# AFE_Channel_1.net
KiCad netlist of a schematic drawn in Altium Designer
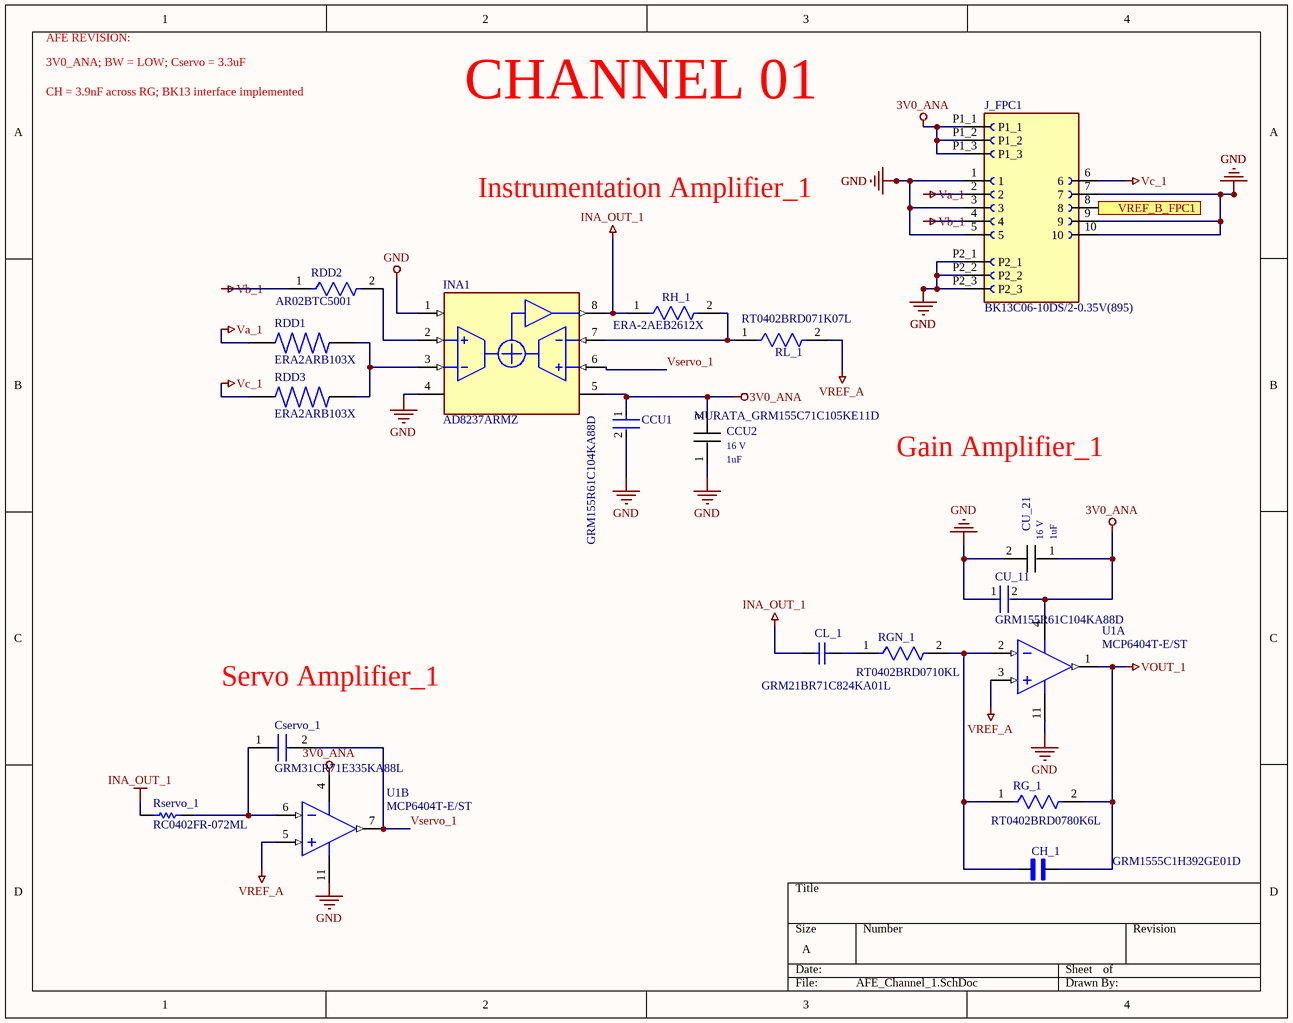
[diagram p0: AFE_Channel_1.SchDoc]

(export (version "E")
  (design (tool "Eeschema 10.0.6"))
  (components
    (comp (ref "CCU1")
      (value "GRM155R61C104KA88D")
      (footprint "96DF66F8-B997-472F-A885-42BCAAE661B2_FP-GRM155-0_05-IPC_C:FP-GRM155-0_05-IPC_C")
      (description "CAP CER 0.1UF 16V X5R 0402")
      (fields (field (name "VOLTAGE") "16V") (field (name "TOLERANCE") "10%"))
      (libsource (lib "EMG_Controlled_R5") (part "EMG_R5_CCU1"))
    )
    (comp (ref "CCU2")
      (value "MURATA_GRM155C71C105KE11D")
      (footprint "MURATA_GRM155C71C105KE11D_0:*MURATA_GRM155C71C105KE11D_0")
      (description "Murata GRM155C71C105KE11D: 1 uF 16 V X7S +/-10%, 0402/1005 metric")
      (fields (field (name "MF") "Murata") (field (name "MP") "GRM155C71C105KE11D"))
      (libsource (lib "EMG_Controlled_R5") (part "EMG_R5_CCU2"))
    )
    (comp (ref "CH_1")
      (value "GRM1555C1H392GE01D")
      (footprint "GRM1555C1H392GE01D_0:CAPC1005X55N")
      (description "SMD capacitor C0G(EIA) with capacitance 3900pF Tol.2%. Rated voltage 50Vdc 125C")
      (fields (field (name "MF") "Murata Electronics"))
      (libsource (lib "EMG_Controlled_R5") (part "EMG_R5_CH_1"))
    )
    (comp (ref "CL_1")
      (value "GRM21BR71C824KA01L")
      (footprint "987105EF-01FA-4198-A59F-44D3B68BB40E_CAPC2013X135X45ML10T25:CAPC2013X135X45ML10T25")
      (fields (field (name "MANUFACTURER") "Murata"))
      (libsource (lib "EMG_Controlled_R5") (part "EMG_R5_CL_1"))
    )
    (comp (ref "Cservo_1")
      (value "GRM31CR71E335KA88L")
      (footprint "SamacSys:GRM31x")
      (description "Capacitor")
      (fields
        (field (name "MOUSER PART NUMBER") "81-GRM31CR71E335KA8L")
        (field (name "MANUFACTURER") "Murata")
      )
      (libsource (lib "EMG_Controlled_R5") (part "EMG_R5_Cservo_1"))
    )
    (comp (ref "CU_11")
      (value "GRM155R61C104KA88D")
      (footprint "96DF66F8-B997-472F-A885-42BCAAE661B2_FP-GRM155-0_05-IPC_C:FP-GRM155-0_05-IPC_C")
      (description "CAP CER 0.1UF 16V X5R 0402")
      (fields (field (name "VOLTAGE") "16V") (field (name "TOLERANCE") "10%"))
      (libsource (lib "EMG_Controlled_R5") (part "EMG_R5_CU_11"))
    )
    (comp (ref "CU_21")
      (value "MURATA_GRM155C71C105KE11D")
      (footprint "MURATA_GRM155C71C105KE11D_0:*MURATA_GRM155C71C105KE11D_0")
      (description "Murata GRM155C71C105KE11D: 1 uF 16 V X7S +/-10%, 0402/1005 metric")
      (fields (field (name "MF") "Murata") (field (name "MP") "GRM155C71C105KE11D"))
      (libsource (lib "EMG_Controlled_R5") (part "EMG_R5_CU_21"))
    )
    (comp (ref "INA1")
      (value "AD8237ARMZ")
      (footprint "EMG_AD8237_R3:EMG_AD8237_R3_MSOP8")
      (description "Micropower, Zero Drift, True Rail-to-Rail Instrumentation Amplifier")
      (fields (field (name "MF") "Analog Devices"))
      (libsource (lib "EMG_Controlled_R5") (part "EMG_R5_INA1"))
    )
    (comp (ref "J_FPC1")
      (value "BK13C06-10DS/2-0.35V(895)")
      (footprint "BK13C06-10DS_2-0.35V_895__0:HIROSE_BK13C06-10DS/2-0.35V(895)")
      (description "10 Position Connector Receptacle, Center Strip Contacts Surface Mount Gold")
      (fields (field (name "MF") "Hirose Electric Co Ltd"))
      (libsource (lib "EMG_Controlled_R5") (part "EMG_R5_J_FPC1"))
    )
    (comp (ref "RDD1")
      (value "ERA2ARB103X")
      (footprint "ERA2ARB103X_0:RES_ERA2ARB103X")
      (libsource (lib "EMG_Controlled_R5") (part "EMG_R5_RDD1"))
    )
    (comp (ref "RDD2")
      (value "AR02BTC5001")
      (footprint "7D606042-220B-45EE-95DD-CA1A974E4C0D_FP-AC0402-MFG:FP-AC0402-MFG")
      (description "-55℃~+155℃ 50V 5kΩ 63mW Thin Film Resistor ±0.1% ±25ppm/℃ 0402 Chip Resistor - Surface Mount ROH")
      (fields
        (field (name "MANUFACTURER") "Viking Tech")
        (field (name "OCTOPART") "https://octopart.com/datasheet/viking-tech/AR02BTC5001")
      )
      (libsource (lib "EMG_Controlled_R5") (part "EMG_R5_RDD2"))
    )
    (comp (ref "RDD3")
      (value "ERA2ARB103X")
      (footprint "ERA2ARB103X_0:RES_ERA2ARB103X")
      (libsource (lib "EMG_Controlled_R5") (part "EMG_R5_RDD3"))
    )
    (comp (ref "RGN_1")
      (value "RT0402BRD0710KL")
      (footprint "B876F212-A29A-4983-9BB8-539D1BA2EBA1_FP-RT0402-MFG:FP-RT0402-MFG")
      (description "RES 10.0K OHM 1/16W .1% SMD 0402")
      (fields
        (field (name "MANUFACTURER") "Yageo")
        (field (name "OCTOPART") "https://octopart.com/rt0402brd0710kl-yageo-1181432")
      )
      (libsource (lib "EMG_Controlled_R5") (part "EMG_R5_RGN_1"))
    )
    (comp (ref "RG_1")
      (value "RT0402BRD0780K6L")
      (footprint "B876F212-A29A-4983-9BB8-539D1BA2EBA1_FP-RT0402-MFG:FP-RT0402-MFG")
      (description "RES SMD 80.6KOHM 0.1% 1/16W 0402")
      (fields
        (field (name "MANUFACTURER") "Yageo")
        (field (name "OCTOPART") "https://octopart.com/rt0402brd0780k6l-yageo-1468076")
      )
      (libsource (lib "EMG_Controlled_R5") (part "EMG_R5_RG_1"))
    )
    (comp (ref "RH_1")
      (value "ERA-2AEB2612X")
      (footprint "1CBBEC27-AD79-48E8-A701-2E235EA9F8F2_FP-AC0402-IPC_A:FP-AC0402-IPC_A")
      (description "RES 26.1kΩ ±0.1% 0.063W 0402")
      (fields (field (name "TOLERANCE") "0.1%") (field (name "MANUFACTURER") "PANASONIC"))
      (libsource (lib "EMG_Controlled_R5") (part "EMG_R5_RH_1"))
    )
    (comp (ref "RL_1")
      (value "RT0402BRD071K07L")
      (footprint "B876F212-A29A-4983-9BB8-539D1BA2EBA1_FP-RT0402-MFG:FP-RT0402-MFG")
      (description "RES SMD 1.07K OHM 0.1% 1/16W")
      (fields
        (field (name "OCTOPART") "https://octopart.com/rt0402brd071k07l-yageo-1400807")
        (field (name "MANUFACTURER") "Yageo")
      )
      (libsource (lib "EMG_Controlled_R5") (part "EMG_R5_RL_1"))
    )
    (comp (ref "Rservo_1")
      (value "RC0402FR-072ML")
      (footprint "3EB15388-1759-44FF-BAE1-1F0823F3E8F1_RESC1005X40X25NL05T10:RESC1005X40X25NL05T10")
      (fields (field (name "MANUFACTURER") "Yageo / Phycomp"))
      (libsource (lib "EMG_Controlled_R5") (part "EMG_R5_Rservo_1"))
    )
    (comp (ref "U1")
      (value "MCP6404T-E/ST")
      (footprint "CEF93338-31F0-4C64-85B6-F650E0BB75E3_TSSOP-ST14_N:TSSOP-ST14_N")
      (description "None")
      (libsource (lib "EMG_Controlled_R5") (part "EMG_R5_U1"))
    )
  )
  (nets
    (net (code "1") (name "/VREF_B_FPC1") (class "Default")
      (node (ref "J_FPC1") (pin "8") (pinfunction "8_8") (pintype "passive"))
    )
    (net (code "2") (name "/Vservo_1") (class "Default")
      (node (ref "Cservo_1") (pin "2") (pinfunction "2_2") (pintype "passive"))
      (node (ref "INA1") (pin "6") (pinfunction "REF_6") (pintype "input"))
      (node (ref "U1") (pin "7") (pinfunction "VOUTB_7") (pintype "output"))
    )
    (net (code "3") (name "3V0_ANA") (class "Default")
      (node (ref "CCU1") (pin "1") (pinfunction "1_1") (pintype "passive"))
      (node (ref "CCU2") (pin "2") (pinfunction "2_2") (pintype "passive"))
      (node (ref "CU_11") (pin "2") (pinfunction "2_2") (pintype "passive"))
      (node (ref "CU_21") (pin "1") (pinfunction "1_1") (pintype "passive"))
      (node (ref "INA1") (pin "5") (pinfunction "+VS_5") (pintype "power_in"))
      (node (ref "J_FPC1") (pin "P1_1") (pinfunction "P1_1_P1_1") (pintype "power_in"))
      (node (ref "J_FPC1") (pin "P1_2") (pinfunction "P1_2_P1_2") (pintype "power_in"))
      (node (ref "J_FPC1") (pin "P1_3") (pinfunction "P1_3_P1_3") (pintype "power_in"))
      (node (ref "U1") (pin "4") (pinfunction "VDD_4") (pintype "power_in"))
    )
    (net (code "4") (name "GND") (class "Default")
      (node (ref "CCU1") (pin "2") (pinfunction "2_2") (pintype "passive"))
      (node (ref "CCU2") (pin "1") (pinfunction "1_1") (pintype "passive"))
      (node (ref "CU_11") (pin "1") (pinfunction "1_1") (pintype "passive"))
      (node (ref "CU_21") (pin "2") (pinfunction "2_2") (pintype "passive"))
      (node (ref "INA1") (pin "1") (pinfunction "BW_1") (pintype "input"))
      (node (ref "INA1") (pin "4") (pinfunction "-VS_4") (pintype "power_in"))
      (node (ref "J_FPC1") (pin "1") (pinfunction "1_1") (pintype "passive"))
      (node (ref "J_FPC1") (pin "10") (pinfunction "10_10") (pintype "passive"))
      (node (ref "J_FPC1") (pin "3") (pinfunction "3_3") (pintype "passive"))
      (node (ref "J_FPC1") (pin "5") (pinfunction "5_5") (pintype "passive"))
      (node (ref "J_FPC1") (pin "7") (pinfunction "7_7") (pintype "passive"))
      (node (ref "J_FPC1") (pin "9") (pinfunction "9_9") (pintype "passive"))
      (node (ref "J_FPC1") (pin "P2_1") (pinfunction "P2_1_P2_1") (pintype "power_in"))
      (node (ref "J_FPC1") (pin "P2_2") (pinfunction "P2_2_P2_2") (pintype "power_in"))
      (node (ref "J_FPC1") (pin "P2_3") (pinfunction "P2_3_P2_3") (pintype "power_in"))
      (node (ref "U1") (pin "11") (pinfunction "VSS_11") (pintype "power_in"))
    )
    (net (code "5") (name "INA_OUT_1") (class "Default")
      (node (ref "CL_1") (pin "2") (pinfunction "2_2") (pintype "passive"))
      (node (ref "INA1") (pin "8") (pinfunction "VOUT_8") (pintype "output"))
      (node (ref "RH_1") (pin "1") (pinfunction "1_1") (pintype "passive"))
      (node (ref "Rservo_1") (pin "2") (pinfunction "2_2") (pintype "passive"))
    )
    (net (code "6") (name "Net-(CL_1-Pad1)") (class "Default")
      (node (ref "CL_1") (pin "1") (pinfunction "1_1") (pintype "passive"))
      (node (ref "RGN_1") (pin "1") (pinfunction "1_1") (pintype "passive"))
    )
    (net (code "7") (name "Net-(INA1-+IN)") (class "Default")
      (node (ref "INA1") (pin "2") (pinfunction "+IN_2") (pintype "input"))
      (node (ref "RDD2") (pin "2") (pinfunction "2_2") (pintype "passive"))
    )
    (net (code "8") (name "Net-(INA1--IN)") (class "Default")
      (node (ref "INA1") (pin "3") (pinfunction "-IN_3") (pintype "input"))
      (node (ref "RDD1") (pin "2") (pinfunction "2_2") (pintype "passive"))
      (node (ref "RDD3") (pin "2") (pinfunction "2_2") (pintype "passive"))
    )
    (net (code "9") (name "Net-(INA1-FB)") (class "Default")
      (node (ref "INA1") (pin "7") (pinfunction "FB_7") (pintype "input"))
      (node (ref "RH_1") (pin "2") (pinfunction "2_2") (pintype "passive"))
      (node (ref "RL_1") (pin "1") (pinfunction "1_1") (pintype "passive"))
    )
    (net (code "10") (name "Net-(U1A-VINA-)") (class "Default")
      (node (ref "CH_1") (pin "2") (pinfunction "2_2") (pintype "passive"))
      (node (ref "RGN_1") (pin "2") (pinfunction "2_2") (pintype "passive"))
      (node (ref "RG_1") (pin "1") (pinfunction "1_1") (pintype "passive"))
      (node (ref "U1") (pin "2") (pinfunction "VINA-_2") (pintype "input"))
    )
    (net (code "11") (name "Net-(U1B-VINB-)") (class "Default")
      (node (ref "Cservo_1") (pin "1") (pinfunction "1_1") (pintype "passive"))
      (node (ref "Rservo_1") (pin "1") (pinfunction "1_1") (pintype "passive"))
      (node (ref "U1") (pin "6") (pinfunction "VINB-_6") (pintype "input"))
    )
    (net (code "12") (name "VOUT_1") (class "Default")
      (node (ref "CH_1") (pin "1") (pinfunction "1_1") (pintype "passive"))
      (node (ref "RG_1") (pin "2") (pinfunction "2_2") (pintype "passive"))
      (node (ref "U1") (pin "1") (pinfunction "VOUTA_1") (pintype "output"))
    )
    (net (code "13") (name "VREF_A") (class "Default")
      (node (ref "RL_1") (pin "2") (pinfunction "2_2") (pintype "passive"))
      (node (ref "U1") (pin "3") (pinfunction "VINA+_3") (pintype "input"))
      (node (ref "U1") (pin "5") (pinfunction "VINB+_5") (pintype "input"))
    )
    (net (code "14") (name "Va_1") (class "Default")
      (node (ref "J_FPC1") (pin "2") (pinfunction "2_2") (pintype "passive"))
      (node (ref "RDD1") (pin "1") (pinfunction "1_1") (pintype "passive"))
    )
    (net (code "15") (name "Vb_1") (class "Default")
      (node (ref "J_FPC1") (pin "4") (pinfunction "4_4") (pintype "passive"))
      (node (ref "RDD2") (pin "1") (pinfunction "1_1") (pintype "passive"))
    )
    (net (code "16") (name "Vc_1") (class "Default")
      (node (ref "J_FPC1") (pin "6") (pinfunction "6_6") (pintype "passive"))
      (node (ref "RDD3") (pin "1") (pinfunction "1_1") (pintype "passive"))
    )
  )
)
